# Sheet-aa.net
KiCad netlist of a schematic drawn in Altium Designer
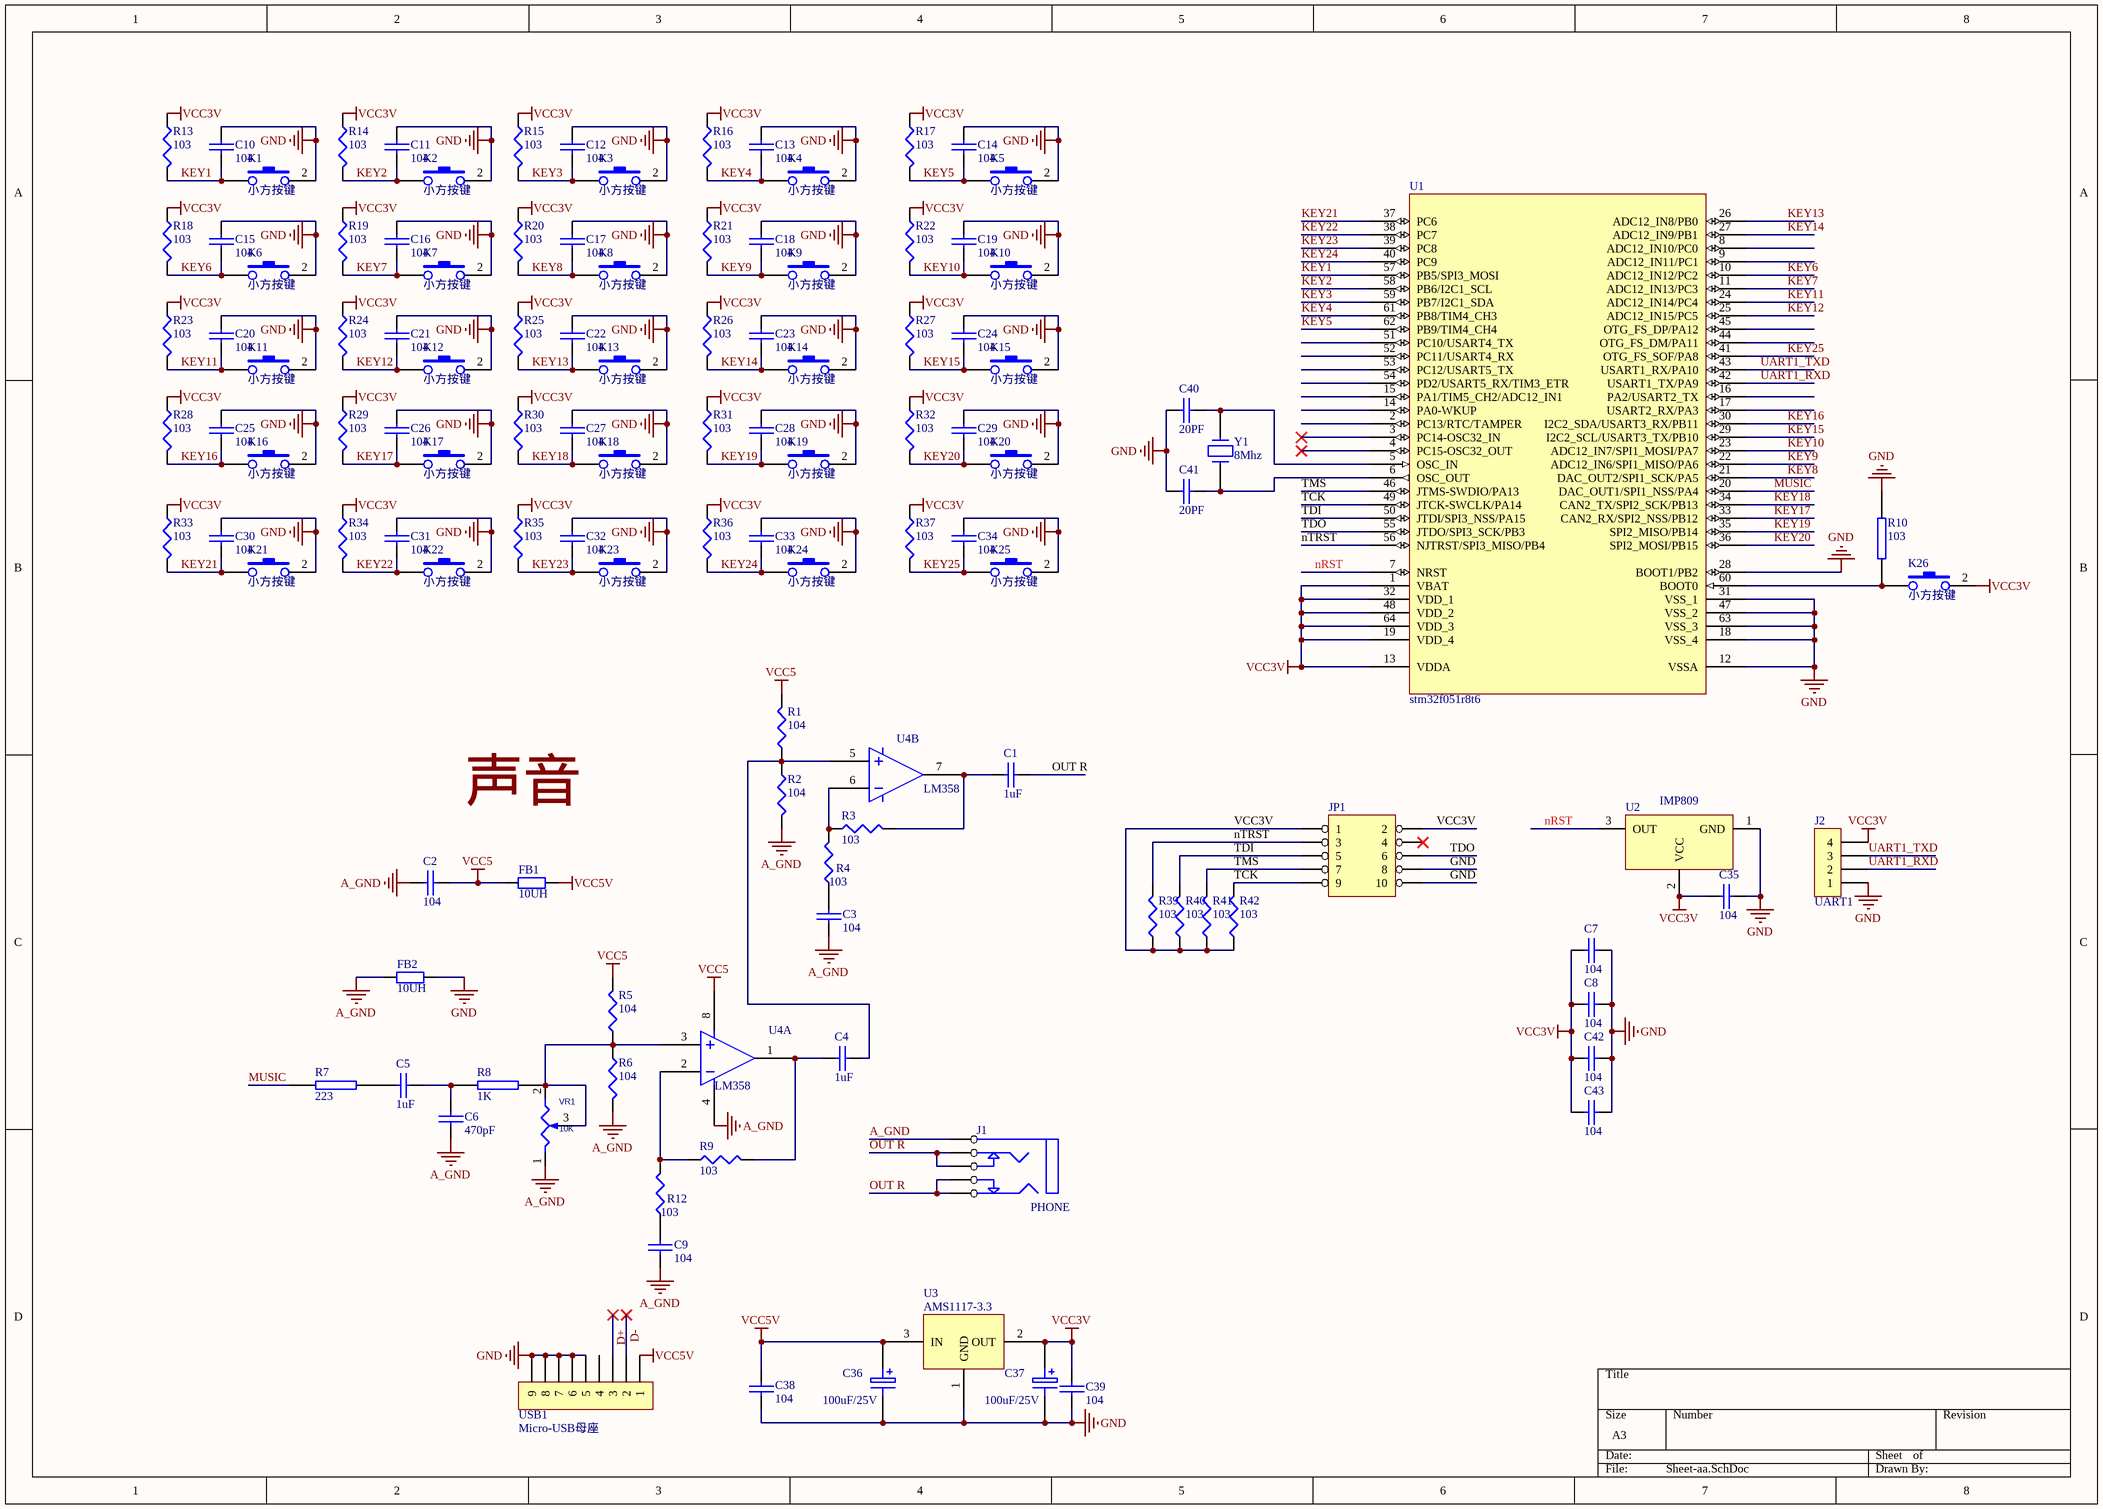
[diagram p0: Sheet-aa.SchDoc]

(export (version "E")
  (design (tool "Eeschema 10.0.6"))
  (components
    (comp (ref "C1")
      (value "1uF")
      (footprint "0805C")
      (description "Capacitor")
      (libsource (lib "*") (part "CAP"))
    )
    (comp (ref "C2")
      (value "104")
      (footprint "0805C")
      (description "Capacitor")
      (libsource (lib "") (part "CAP_1"))
    )
    (comp (ref "C3")
      (value "104")
      (footprint "0805C")
      (description "Capacitor")
      (libsource (lib "*") (part "CAP"))
    )
    (comp (ref "C4")
      (value "1uF")
      (footprint "0805C")
      (description "Capacitor")
      (libsource (lib "*") (part "CAP"))
    )
    (comp (ref "C5")
      (value "1uF")
      (footprint "0805C")
      (description "Capacitor")
      (libsource (lib "*") (part "CAP"))
    )
    (comp (ref "C6")
      (value "470pF")
      (footprint "0805C")
      (description "Capacitor")
      (libsource (lib "*") (part "CAP"))
    )
    (comp (ref "C7") (value "104") (description "Capacitor") (libsource (lib "常用分立器件") (part "CAP")))
    (comp (ref "C8") (value "104") (description "Capacitor") (libsource (lib "常用分立器件") (part "CAP")))
    (comp (ref "C9")
      (value "104")
      (footprint "0805C")
      (description "Capacitor")
      (libsource (lib "*") (part "CAP"))
    )
    (comp (ref "C10")
      (value "104")
      (footprint "0805C")
      (description "Capacitor")
      (libsource (lib "*") (part "CAP"))
    )
    (comp (ref "C11")
      (value "104")
      (footprint "0805C")
      (description "Capacitor")
      (libsource (lib "*") (part "CAP"))
    )
    (comp (ref "C12")
      (value "104")
      (footprint "0805C")
      (description "Capacitor")
      (libsource (lib "*") (part "CAP"))
    )
    (comp (ref "C13")
      (value "104")
      (footprint "0805C")
      (description "Capacitor")
      (libsource (lib "*") (part "CAP"))
    )
    (comp (ref "C14")
      (value "104")
      (footprint "0805C")
      (description "Capacitor")
      (libsource (lib "*") (part "CAP"))
    )
    (comp (ref "C15")
      (value "104")
      (footprint "0805C")
      (description "Capacitor")
      (libsource (lib "*") (part "CAP"))
    )
    (comp (ref "C16")
      (value "104")
      (footprint "0805C")
      (description "Capacitor")
      (libsource (lib "*") (part "CAP"))
    )
    (comp (ref "C17")
      (value "104")
      (footprint "0805C")
      (description "Capacitor")
      (libsource (lib "*") (part "CAP"))
    )
    (comp (ref "C18")
      (value "104")
      (footprint "0805C")
      (description "Capacitor")
      (libsource (lib "*") (part "CAP"))
    )
    (comp (ref "C19")
      (value "104")
      (footprint "0805C")
      (description "Capacitor")
      (libsource (lib "*") (part "CAP"))
    )
    (comp (ref "C20")
      (value "104")
      (footprint "0805C")
      (description "Capacitor")
      (libsource (lib "*") (part "CAP"))
    )
    (comp (ref "C21")
      (value "104")
      (footprint "0805C")
      (description "Capacitor")
      (libsource (lib "*") (part "CAP"))
    )
    (comp (ref "C22")
      (value "104")
      (footprint "0805C")
      (description "Capacitor")
      (libsource (lib "*") (part "CAP"))
    )
    (comp (ref "C23")
      (value "104")
      (footprint "0805C")
      (description "Capacitor")
      (libsource (lib "*") (part "CAP"))
    )
    (comp (ref "C24")
      (value "104")
      (footprint "0805C")
      (description "Capacitor")
      (libsource (lib "*") (part "CAP"))
    )
    (comp (ref "C25")
      (value "104")
      (footprint "0805C")
      (description "Capacitor")
      (libsource (lib "*") (part "CAP"))
    )
    (comp (ref "C26")
      (value "104")
      (footprint "0805C")
      (description "Capacitor")
      (libsource (lib "*") (part "CAP"))
    )
    (comp (ref "C27")
      (value "104")
      (footprint "0805C")
      (description "Capacitor")
      (libsource (lib "*") (part "CAP"))
    )
    (comp (ref "C28")
      (value "104")
      (footprint "0805C")
      (description "Capacitor")
      (libsource (lib "*") (part "CAP"))
    )
    (comp (ref "C29")
      (value "104")
      (footprint "0805C")
      (description "Capacitor")
      (libsource (lib "*") (part "CAP"))
    )
    (comp (ref "C30")
      (value "104")
      (footprint "0805C")
      (description "Capacitor")
      (libsource (lib "*") (part "CAP"))
    )
    (comp (ref "C31")
      (value "104")
      (footprint "0805C")
      (description "Capacitor")
      (libsource (lib "*") (part "CAP"))
    )
    (comp (ref "C32")
      (value "104")
      (footprint "0805C")
      (description "Capacitor")
      (libsource (lib "*") (part "CAP"))
    )
    (comp (ref "C33")
      (value "104")
      (footprint "0805C")
      (description "Capacitor")
      (libsource (lib "*") (part "CAP"))
    )
    (comp (ref "C34")
      (value "104")
      (footprint "0805C")
      (description "Capacitor")
      (libsource (lib "*") (part "CAP"))
    )
    (comp (ref "C35") (value "104") (description "Capacitor") (libsource (lib "常用分立器件") (part "CAP")))
    (comp (ref "C36")
      (value "100uF/25V")
      (footprint "1016V")
      (description "Electrolytic Capacitor")
      (libsource (lib "*") (part "ELECTRO1"))
    )
    (comp (ref "C37")
      (value "100uF/25V")
      (footprint "1016V")
      (description "Electrolytic Capacitor")
      (libsource (lib "*") (part "ELECTRO1"))
    )
    (comp (ref "C38")
      (value "104")
      (footprint "0805C")
      (description "Capacitor")
      (libsource (lib "") (part "CAP_1"))
    )
    (comp (ref "C39")
      (value "104")
      (footprint "0805C")
      (description "Capacitor")
      (libsource (lib "") (part "CAP_1"))
    )
    (comp (ref "C40")
      (value "20PF")
      (footprint "0805C")
      (description "Capacitor")
      (libsource (lib "常用分立器件") (part "CAP"))
    )
    (comp (ref "C41")
      (value "20PF")
      (footprint "0805C")
      (description "Capacitor")
      (libsource (lib "常用分立器件") (part "CAP"))
    )
    (comp (ref "C42") (value "104") (description "Capacitor") (libsource (lib "常用分立器件") (part "CAP")))
    (comp (ref "C43") (value "104") (description "Capacitor") (libsource (lib "常用分立器件") (part "CAP")))
    (comp (ref "FB1")
      (value "10UH")
      (footprint "0805")
      (description "Resistor")
      (fields (field (name "Comment") "Res2") (field (name "PUBLISHER") "Altium Limited"))
      (libsource (lib "Miscellaneous Devices") (part "Res2"))
    )
    (comp (ref "FB2")
      (value "10UH")
      (footprint "0805")
      (description "Resistor")
      (fields (field (name "Comment") "Res2") (field (name "PUBLISHER") "Altium Limited"))
      (libsource (lib "Miscellaneous Devices") (part "Res2"))
    )
    (comp (ref "J1") (value "PHONE") (footprint "SOUND-2") (libsource (lib "*") (part "PHONEJACK STEREO SW")))
    (comp (ref "J2")
      (value "UART1")
      (footprint "4SIP4")
      (description "Connector")
      (libsource (lib "*") (part "CON4"))
    )
    (comp (ref "JP1") (value "~") (footprint "JYNJ_10") (libsource (lib "*") (part "HEADER 5X2")))
    (comp (ref "K1")
      (value "小方按键")
      (footprint "4KEY-1")
      (description "小方按键6*6")
      (libsource (lib "常用") (part "SW-PB"))
    )
    (comp (ref "K2")
      (value "小方按键")
      (footprint "4KEY-1")
      (description "小方按键6*6")
      (libsource (lib "常用") (part "SW-PB"))
    )
    (comp (ref "K3")
      (value "小方按键")
      (footprint "4KEY-1")
      (description "小方按键6*6")
      (libsource (lib "常用") (part "SW-PB"))
    )
    (comp (ref "K4")
      (value "小方按键")
      (footprint "4KEY-1")
      (description "小方按键6*6")
      (libsource (lib "常用") (part "SW-PB"))
    )
    (comp (ref "K5")
      (value "小方按键")
      (footprint "4KEY-1")
      (description "小方按键6*6")
      (libsource (lib "常用") (part "SW-PB"))
    )
    (comp (ref "K6")
      (value "小方按键")
      (footprint "4KEY-1")
      (description "小方按键6*6")
      (libsource (lib "常用") (part "SW-PB"))
    )
    (comp (ref "K7")
      (value "小方按键")
      (footprint "4KEY-1")
      (description "小方按键6*6")
      (libsource (lib "常用") (part "SW-PB"))
    )
    (comp (ref "K8")
      (value "小方按键")
      (footprint "4KEY-1")
      (description "小方按键6*6")
      (libsource (lib "常用") (part "SW-PB"))
    )
    (comp (ref "K9")
      (value "小方按键")
      (footprint "4KEY-1")
      (description "小方按键6*6")
      (libsource (lib "常用") (part "SW-PB"))
    )
    (comp (ref "K10")
      (value "小方按键")
      (footprint "4KEY-1")
      (description "小方按键6*6")
      (libsource (lib "常用") (part "SW-PB"))
    )
    (comp (ref "K11")
      (value "小方按键")
      (footprint "4KEY-1")
      (description "小方按键6*6")
      (libsource (lib "常用") (part "SW-PB"))
    )
    (comp (ref "K12")
      (value "小方按键")
      (footprint "4KEY-1")
      (description "小方按键6*6")
      (libsource (lib "常用") (part "SW-PB"))
    )
    (comp (ref "K13")
      (value "小方按键")
      (footprint "4KEY-1")
      (description "小方按键6*6")
      (libsource (lib "常用") (part "SW-PB"))
    )
    (comp (ref "K14")
      (value "小方按键")
      (footprint "4KEY-1")
      (description "小方按键6*6")
      (libsource (lib "常用") (part "SW-PB"))
    )
    (comp (ref "K15")
      (value "小方按键")
      (footprint "4KEY-1")
      (description "小方按键6*6")
      (libsource (lib "常用") (part "SW-PB"))
    )
    (comp (ref "K16")
      (value "小方按键")
      (footprint "4KEY-1")
      (description "小方按键6*6")
      (libsource (lib "常用") (part "SW-PB"))
    )
    (comp (ref "K17")
      (value "小方按键")
      (footprint "4KEY-1")
      (description "小方按键6*6")
      (libsource (lib "常用") (part "SW-PB"))
    )
    (comp (ref "K18")
      (value "小方按键")
      (footprint "4KEY-1")
      (description "小方按键6*6")
      (libsource (lib "常用") (part "SW-PB"))
    )
    (comp (ref "K19")
      (value "小方按键")
      (footprint "4KEY-1")
      (description "小方按键6*6")
      (libsource (lib "常用") (part "SW-PB"))
    )
    (comp (ref "K20")
      (value "小方按键")
      (footprint "4KEY-1")
      (description "小方按键6*6")
      (libsource (lib "常用") (part "SW-PB"))
    )
    (comp (ref "K21")
      (value "小方按键")
      (footprint "4KEY-1")
      (description "小方按键6*6")
      (libsource (lib "常用") (part "SW-PB"))
    )
    (comp (ref "K22")
      (value "小方按键")
      (footprint "4KEY-1")
      (description "小方按键6*6")
      (libsource (lib "常用") (part "SW-PB"))
    )
    (comp (ref "K23")
      (value "小方按键")
      (footprint "4KEY-1")
      (description "小方按键6*6")
      (libsource (lib "常用") (part "SW-PB"))
    )
    (comp (ref "K24")
      (value "小方按键")
      (footprint "4KEY-1")
      (description "小方按键6*6")
      (libsource (lib "常用") (part "SW-PB"))
    )
    (comp (ref "K25")
      (value "小方按键")
      (footprint "4KEY-1")
      (description "小方按键6*6")
      (libsource (lib "常用") (part "SW-PB"))
    )
    (comp (ref "K26")
      (value "小方按键")
      (footprint "4KEY-1")
      (description "小方按键6*6")
      (libsource (lib "常用") (part "SW-PB"))
    )
    (comp (ref "R1")
      (value "104")
      (footprint "0805R")
      (description "直插电阻")
      (libsource (lib "常用") (part "RES1"))
    )
    (comp (ref "R2")
      (value "104")
      (footprint "0805R")
      (description "直插电阻")
      (libsource (lib "常用") (part "RES1"))
    )
    (comp (ref "R3")
      (value "103")
      (footprint "0805R")
      (description "直插电阻")
      (libsource (lib "常用") (part "RES1"))
    )
    (comp (ref "R4")
      (value "103")
      (footprint "0805R")
      (description "直插电阻")
      (libsource (lib "常用") (part "RES1"))
    )
    (comp (ref "R5")
      (value "104")
      (footprint "0805R")
      (description "直插电阻")
      (libsource (lib "常用") (part "RES1"))
    )
    (comp (ref "R6")
      (value "104")
      (footprint "0805R")
      (description "直插电阻")
      (libsource (lib "常用") (part "RES1"))
    )
    (comp (ref "R7") (value "223") (footprint "0805R") (libsource (lib "*") (part "RES2")))
    (comp (ref "R8") (value "1K") (footprint "0805R") (libsource (lib "*") (part "RES2")))
    (comp (ref "R9")
      (value "103")
      (footprint "0805R")
      (description "直插电阻")
      (libsource (lib "常用") (part "RES1"))
    )
    (comp (ref "R10") (value "103") (footprint "0805R") (libsource (lib "*") (part "RES2")))
    (comp (ref "R12")
      (value "103")
      (footprint "0805R")
      (description "直插电阻")
      (libsource (lib "常用") (part "RES1"))
    )
    (comp (ref "R13")
      (value "103")
      (footprint "0805R")
      (description "直插电阻")
      (libsource (lib "常用") (part "RES1"))
    )
    (comp (ref "R14")
      (value "103")
      (footprint "0805R")
      (description "直插电阻")
      (libsource (lib "常用") (part "RES1"))
    )
    (comp (ref "R15")
      (value "103")
      (footprint "0805R")
      (description "直插电阻")
      (libsource (lib "常用") (part "RES1"))
    )
    (comp (ref "R16")
      (value "103")
      (footprint "0805R")
      (description "直插电阻")
      (libsource (lib "常用") (part "RES1"))
    )
    (comp (ref "R17")
      (value "103")
      (footprint "0805R")
      (description "直插电阻")
      (libsource (lib "常用") (part "RES1"))
    )
    (comp (ref "R18")
      (value "103")
      (footprint "0805R")
      (description "直插电阻")
      (libsource (lib "常用") (part "RES1"))
    )
    (comp (ref "R19")
      (value "103")
      (footprint "0805R")
      (description "直插电阻")
      (libsource (lib "常用") (part "RES1"))
    )
    (comp (ref "R20")
      (value "103")
      (footprint "0805R")
      (description "直插电阻")
      (libsource (lib "常用") (part "RES1"))
    )
    (comp (ref "R21")
      (value "103")
      (footprint "0805R")
      (description "直插电阻")
      (libsource (lib "常用") (part "RES1"))
    )
    (comp (ref "R22")
      (value "103")
      (footprint "0805R")
      (description "直插电阻")
      (libsource (lib "常用") (part "RES1"))
    )
    (comp (ref "R23")
      (value "103")
      (footprint "0805R")
      (description "直插电阻")
      (libsource (lib "常用") (part "RES1"))
    )
    (comp (ref "R24")
      (value "103")
      (footprint "0805R")
      (description "直插电阻")
      (libsource (lib "常用") (part "RES1"))
    )
    (comp (ref "R25")
      (value "103")
      (footprint "0805R")
      (description "直插电阻")
      (libsource (lib "常用") (part "RES1"))
    )
    (comp (ref "R26")
      (value "103")
      (footprint "0805R")
      (description "直插电阻")
      (libsource (lib "常用") (part "RES1"))
    )
    (comp (ref "R27")
      (value "103")
      (footprint "0805R")
      (description "直插电阻")
      (libsource (lib "常用") (part "RES1"))
    )
    (comp (ref "R28")
      (value "103")
      (footprint "0805R")
      (description "直插电阻")
      (libsource (lib "常用") (part "RES1"))
    )
    (comp (ref "R29")
      (value "103")
      (footprint "0805R")
      (description "直插电阻")
      (libsource (lib "常用") (part "RES1"))
    )
    (comp (ref "R30")
      (value "103")
      (footprint "0805R")
      (description "直插电阻")
      (libsource (lib "常用") (part "RES1"))
    )
    (comp (ref "R31")
      (value "103")
      (footprint "0805R")
      (description "直插电阻")
      (libsource (lib "常用") (part "RES1"))
    )
    (comp (ref "R32")
      (value "103")
      (footprint "0805R")
      (description "直插电阻")
      (libsource (lib "常用") (part "RES1"))
    )
    (comp (ref "R33")
      (value "103")
      (footprint "0805R")
      (description "直插电阻")
      (libsource (lib "常用") (part "RES1"))
    )
    (comp (ref "R34")
      (value "103")
      (footprint "0805R")
      (description "直插电阻")
      (libsource (lib "常用") (part "RES1"))
    )
    (comp (ref "R35")
      (value "103")
      (footprint "0805R")
      (description "直插电阻")
      (libsource (lib "常用") (part "RES1"))
    )
    (comp (ref "R36")
      (value "103")
      (footprint "0805R")
      (description "直插电阻")
      (libsource (lib "常用") (part "RES1"))
    )
    (comp (ref "R37")
      (value "103")
      (footprint "0805R")
      (description "直插电阻")
      (libsource (lib "常用") (part "RES1"))
    )
    (comp (ref "R39")
      (value "103")
      (footprint "0805R")
      (description "直插电阻")
      (libsource (lib "常用") (part "RES1"))
    )
    (comp (ref "R40")
      (value "103")
      (footprint "0805R")
      (description "直插电阻")
      (libsource (lib "常用") (part "RES1"))
    )
    (comp (ref "R41")
      (value "103")
      (footprint "0805R")
      (description "直插电阻")
      (libsource (lib "常用") (part "RES1"))
    )
    (comp (ref "R42")
      (value "103")
      (footprint "0805R")
      (description "直插电阻")
      (libsource (lib "常用") (part "RES1"))
    )
    (comp (ref "U1")
      (value "stm32f051r8t6")
      (footprint "LC-LQFP-64_10x10x05P")
      (description "32位STM单片机")
      (fields (field (name "版权归属") "源创客"))
      (libsource (lib "2.1   - STM32系列单片机") (part "STM32F105RB_1"))
    )
    (comp (ref "U2") (value "IMP809") (footprint "SOT23") (libsource (lib "常用分立器件") (part "IMP809")))
    (comp (ref "U3") (value "AMS1117-3.3") (footprint "to-252") (libsource (lib "*") (part "LM1117")))
    (comp (ref "U4") (value "LM358") (footprint "SOP8") (libsource (lib "*") (part "LM139")))
    (comp (ref "USB1")
      (value "Micro-USB母座")
      (footprint "Micro-USB")
      (description "Connector")
      (libsource (lib "接口端子类") (part "CON9"))
    )
    (comp (ref "VR1") (value "10K") (libsource (lib "*") (part "RESISTOR VAR")))
    (comp (ref "Y1")
      (value "8Mhz")
      (footprint "2XTAL")
      (description "Crystal")
      (libsource (lib "常用分立器件") (part "CRYSTAL"))
    )
  )
  (nets
    (net (code "1") (name "/D+") (class "Default")
      (node (ref "USB1") (pin "3") (pinfunction "3_3") (pintype "passive+no_connect"))
    )
    (net (code "2") (name "/D-") (class "Default")
      (node (ref "USB1") (pin "2") (pinfunction "2_2") (pintype "passive+no_connect"))
    )
    (net (code "3") (name "/KEY1") (class "Default")
      (node (ref "C10") (pin "2") (pinfunction "2_2") (pintype "passive"))
      (node (ref "K1") (pin "1") (pinfunction "1_1") (pintype "passive"))
      (node (ref "R13") (pin "2") (pintype "passive"))
      (node (ref "U1") (pin "57") (pinfunction "PB5/SPI3_MOSI_57") (pintype "bidirectional"))
    )
    (net (code "4") (name "/KEY2") (class "Default")
      (node (ref "C11") (pin "2") (pinfunction "2_2") (pintype "passive"))
      (node (ref "K2") (pin "1") (pinfunction "1_1") (pintype "passive"))
      (node (ref "R14") (pin "2") (pintype "passive"))
      (node (ref "U1") (pin "58") (pinfunction "PB6/I2C1_SCL_58") (pintype "bidirectional"))
    )
    (net (code "5") (name "/KEY3") (class "Default")
      (node (ref "C12") (pin "2") (pinfunction "2_2") (pintype "passive"))
      (node (ref "K3") (pin "1") (pinfunction "1_1") (pintype "passive"))
      (node (ref "R15") (pin "2") (pintype "passive"))
      (node (ref "U1") (pin "59") (pinfunction "PB7/I2C1_SDA_59") (pintype "bidirectional"))
    )
    (net (code "6") (name "/KEY4") (class "Default")
      (node (ref "C13") (pin "2") (pinfunction "2_2") (pintype "passive"))
      (node (ref "K4") (pin "1") (pinfunction "1_1") (pintype "passive"))
      (node (ref "R16") (pin "2") (pintype "passive"))
      (node (ref "U1") (pin "61") (pinfunction "PB8/TIM4_CH3_61") (pintype "bidirectional"))
    )
    (net (code "7") (name "/KEY5") (class "Default")
      (node (ref "C14") (pin "2") (pinfunction "2_2") (pintype "passive"))
      (node (ref "K5") (pin "1") (pinfunction "1_1") (pintype "passive"))
      (node (ref "R17") (pin "2") (pintype "passive"))
      (node (ref "U1") (pin "62") (pinfunction "PB9/TIM4_CH4_62") (pintype "bidirectional"))
    )
    (net (code "8") (name "/KEY6") (class "Default")
      (node (ref "C15") (pin "2") (pinfunction "2_2") (pintype "passive"))
      (node (ref "K6") (pin "1") (pinfunction "1_1") (pintype "passive"))
      (node (ref "R18") (pin "2") (pintype "passive"))
      (node (ref "U1") (pin "10") (pinfunction "ADC12_IN12/PC2_10") (pintype "bidirectional"))
    )
    (net (code "9") (name "/KEY7") (class "Default")
      (node (ref "C16") (pin "2") (pinfunction "2_2") (pintype "passive"))
      (node (ref "K7") (pin "1") (pinfunction "1_1") (pintype "passive"))
      (node (ref "R19") (pin "2") (pintype "passive"))
      (node (ref "U1") (pin "11") (pinfunction "ADC12_IN13/PC3_11") (pintype "bidirectional"))
    )
    (net (code "10") (name "/KEY8") (class "Default")
      (node (ref "C17") (pin "2") (pinfunction "2_2") (pintype "passive"))
      (node (ref "K8") (pin "1") (pinfunction "1_1") (pintype "passive"))
      (node (ref "R20") (pin "2") (pintype "passive"))
      (node (ref "U1") (pin "21") (pinfunction "DAC_OUT2/SPI1_SCK/PA5_21") (pintype "bidirectional"))
    )
    (net (code "11") (name "/KEY9") (class "Default")
      (node (ref "C18") (pin "2") (pinfunction "2_2") (pintype "passive"))
      (node (ref "K9") (pin "1") (pinfunction "1_1") (pintype "passive"))
      (node (ref "R21") (pin "2") (pintype "passive"))
      (node (ref "U1") (pin "22") (pinfunction "ADC12_IN6/SPI1_MISO/PA6_22") (pintype "bidirectional"))
    )
    (net (code "12") (name "/KEY10") (class "Default")
      (node (ref "C19") (pin "2") (pinfunction "2_2") (pintype "passive"))
      (node (ref "K10") (pin "1") (pinfunction "1_1") (pintype "passive"))
      (node (ref "R22") (pin "2") (pintype "passive"))
      (node (ref "U1") (pin "23") (pinfunction "ADC12_IN7/SPI1_MOSI/PA7_23") (pintype "bidirectional"))
    )
    (net (code "13") (name "/KEY11") (class "Default")
      (node (ref "C20") (pin "2") (pinfunction "2_2") (pintype "passive"))
      (node (ref "K11") (pin "1") (pinfunction "1_1") (pintype "passive"))
      (node (ref "R23") (pin "2") (pintype "passive"))
      (node (ref "U1") (pin "24") (pinfunction "ADC12_IN14/PC4_24") (pintype "bidirectional"))
    )
    (net (code "14") (name "/KEY12") (class "Default")
      (node (ref "C21") (pin "2") (pinfunction "2_2") (pintype "passive"))
      (node (ref "K12") (pin "1") (pinfunction "1_1") (pintype "passive"))
      (node (ref "R24") (pin "2") (pintype "passive"))
      (node (ref "U1") (pin "25") (pinfunction "ADC12_IN15/PC5_25") (pintype "bidirectional"))
    )
    (net (code "15") (name "/KEY13") (class "Default")
      (node (ref "C22") (pin "2") (pinfunction "2_2") (pintype "passive"))
      (node (ref "K13") (pin "1") (pinfunction "1_1") (pintype "passive"))
      (node (ref "R25") (pin "2") (pintype "passive"))
      (node (ref "U1") (pin "26") (pinfunction "ADC12_IN8/PB0_26") (pintype "bidirectional"))
    )
    (net (code "16") (name "/KEY14") (class "Default")
      (node (ref "C23") (pin "2") (pinfunction "2_2") (pintype "passive"))
      (node (ref "K14") (pin "1") (pinfunction "1_1") (pintype "passive"))
      (node (ref "R26") (pin "2") (pintype "passive"))
      (node (ref "U1") (pin "27") (pinfunction "ADC12_IN9/PB1_27") (pintype "bidirectional"))
    )
    (net (code "17") (name "/KEY15") (class "Default")
      (node (ref "C24") (pin "2") (pinfunction "2_2") (pintype "passive"))
      (node (ref "K15") (pin "1") (pinfunction "1_1") (pintype "passive"))
      (node (ref "R27") (pin "2") (pintype "passive"))
      (node (ref "U1") (pin "29") (pinfunction "I2C2_SCL/USART3_TX/PB10_29") (pintype "bidirectional"))
    )
    (net (code "18") (name "/KEY16") (class "Default")
      (node (ref "C25") (pin "2") (pinfunction "2_2") (pintype "passive"))
      (node (ref "K16") (pin "1") (pinfunction "1_1") (pintype "passive"))
      (node (ref "R28") (pin "2") (pintype "passive"))
      (node (ref "U1") (pin "30") (pinfunction "I2C2_SDA/USART3_RX/PB11_30") (pintype "bidirectional"))
    )
    (net (code "19") (name "/KEY17") (class "Default")
      (node (ref "C26") (pin "2") (pinfunction "2_2") (pintype "passive"))
      (node (ref "K17") (pin "1") (pinfunction "1_1") (pintype "passive"))
      (node (ref "R29") (pin "2") (pintype "passive"))
      (node (ref "U1") (pin "33") (pinfunction "CAN2_RX/SPI2_NSS/PB12_33") (pintype "bidirectional"))
    )
    (net (code "20") (name "/KEY18") (class "Default")
      (node (ref "C27") (pin "2") (pinfunction "2_2") (pintype "passive"))
      (node (ref "K18") (pin "1") (pinfunction "1_1") (pintype "passive"))
      (node (ref "R30") (pin "2") (pintype "passive"))
      (node (ref "U1") (pin "34") (pinfunction "CAN2_TX/SPI2_SCK/PB13_34") (pintype "bidirectional"))
    )
    (net (code "21") (name "/KEY19") (class "Default")
      (node (ref "C28") (pin "2") (pinfunction "2_2") (pintype "passive"))
      (node (ref "K19") (pin "1") (pinfunction "1_1") (pintype "passive"))
      (node (ref "R31") (pin "2") (pintype "passive"))
      (node (ref "U1") (pin "35") (pinfunction "SPI2_MISO/PB14_35") (pintype "bidirectional"))
    )
    (net (code "22") (name "/KEY20") (class "Default")
      (node (ref "C29") (pin "2") (pinfunction "2_2") (pintype "passive"))
      (node (ref "K20") (pin "1") (pinfunction "1_1") (pintype "passive"))
      (node (ref "R32") (pin "2") (pintype "passive"))
      (node (ref "U1") (pin "36") (pinfunction "SPI2_MOSI/PB15_36") (pintype "bidirectional"))
    )
    (net (code "23") (name "/KEY21") (class "Default")
      (node (ref "C30") (pin "2") (pinfunction "2_2") (pintype "passive"))
      (node (ref "K21") (pin "1") (pinfunction "1_1") (pintype "passive"))
      (node (ref "R33") (pin "2") (pintype "passive"))
      (node (ref "U1") (pin "37") (pinfunction "PC6_37") (pintype "bidirectional"))
    )
    (net (code "24") (name "/KEY22") (class "Default")
      (node (ref "C31") (pin "2") (pinfunction "2_2") (pintype "passive"))
      (node (ref "K22") (pin "1") (pinfunction "1_1") (pintype "passive"))
      (node (ref "R34") (pin "2") (pintype "passive"))
      (node (ref "U1") (pin "38") (pinfunction "PC7_38") (pintype "bidirectional"))
    )
    (net (code "25") (name "/KEY23") (class "Default")
      (node (ref "C32") (pin "2") (pinfunction "2_2") (pintype "passive"))
      (node (ref "K23") (pin "1") (pinfunction "1_1") (pintype "passive"))
      (node (ref "R35") (pin "2") (pintype "passive"))
      (node (ref "U1") (pin "39") (pinfunction "PC8_39") (pintype "bidirectional"))
    )
    (net (code "26") (name "/KEY24") (class "Default")
      (node (ref "C33") (pin "2") (pinfunction "2_2") (pintype "passive"))
      (node (ref "K24") (pin "1") (pinfunction "1_1") (pintype "passive"))
      (node (ref "R36") (pin "2") (pintype "passive"))
      (node (ref "U1") (pin "40") (pinfunction "PC9_40") (pintype "bidirectional"))
    )
    (net (code "27") (name "/KEY25") (class "Default")
      (node (ref "C34") (pin "2") (pinfunction "2_2") (pintype "passive"))
      (node (ref "K25") (pin "1") (pinfunction "1_1") (pintype "passive"))
      (node (ref "R37") (pin "2") (pintype "passive"))
      (node (ref "U1") (pin "41") (pinfunction "OTG_FS_SOF/PA8_41") (pintype "bidirectional"))
    )
    (net (code "28") (name "/MUSIC") (class "Default")
      (node (ref "R7") (pin "1") (pinfunction "1_1") (pintype "passive"))
      (node (ref "U1") (pin "20") (pinfunction "DAC_OUT1/SPI1_NSS/PA4_20") (pintype "bidirectional"))
    )
    (net (code "29") (name "/OUT R") (class "Default")
      (node (ref "C1") (pin "1") (pinfunction "1_1") (pintype "passive"))
      (node (ref "J1") (pin "1") (pinfunction "A_1") (pintype "passive"))
      (node (ref "J1") (pin "2") (pinfunction "B_2") (pintype "passive"))
      (node (ref "J1") (pin "3") (pinfunction "C_3") (pintype "passive"))
      (node (ref "J1") (pin "4") (pinfunction "D_4") (pintype "passive"))
    )
    (net (code "30") (name "/TCK") (class "Default")
      (node (ref "JP1") (pin "9") (pinfunction "9_9") (pintype "passive"))
      (node (ref "R42") (pin "2") (pintype "passive"))
      (node (ref "U1") (pin "49") (pinfunction "JTCK-SWCLK/PA14_49") (pintype "bidirectional"))
    )
    (net (code "31") (name "/TDI") (class "Default")
      (node (ref "JP1") (pin "5") (pinfunction "5_5") (pintype "passive"))
      (node (ref "R40") (pin "2") (pintype "passive"))
      (node (ref "U1") (pin "50") (pinfunction "JTDI/SPI3_NSS/PA15_50") (pintype "bidirectional"))
    )
    (net (code "32") (name "/TDO") (class "Default")
      (node (ref "JP1") (pin "6") (pinfunction "6_6") (pintype "passive"))
      (node (ref "U1") (pin "55") (pinfunction "JTDO/SPI3_SCK/PB3_55") (pintype "bidirectional"))
    )
    (net (code "33") (name "/TMS") (class "Default")
      (node (ref "JP1") (pin "7") (pinfunction "7_7") (pintype "passive"))
      (node (ref "R41") (pin "2") (pintype "passive"))
      (node (ref "U1") (pin "46") (pinfunction "JTMS-SWDIO/PA13_46") (pintype "bidirectional"))
    )
    (net (code "34") (name "/UART1_RXD") (class "Default")
      (node (ref "J2") (pin "2") (pinfunction "2_2") (pintype "passive"))
      (node (ref "U1") (pin "42") (pinfunction "USART1_TX/PA9_42") (pintype "bidirectional"))
    )
    (net (code "35") (name "/UART1_TXD") (class "Default")
      (node (ref "J2") (pin "3") (pinfunction "3_3") (pintype "passive"))
      (node (ref "U1") (pin "43") (pinfunction "USART1_RX/PA10_43") (pintype "bidirectional"))
    )
    (net (code "36") (name "/nRST") (class "Default")
      (node (ref "U1") (pin "7") (pinfunction "NRST_7") (pintype "bidirectional"))
      (node (ref "U2") (pin "3") (pinfunction "OUT_3") (pintype "passive"))
    )
    (net (code "37") (name "/nTRST") (class "Default")
      (node (ref "JP1") (pin "3") (pinfunction "3_3") (pintype "passive"))
      (node (ref "R39") (pin "2") (pintype "passive"))
      (node (ref "U1") (pin "56") (pinfunction "NJTRST/SPI3_MISO/PB4_56") (pintype "bidirectional"))
    )
    (net (code "38") (name "A_GND") (class "Default")
      (node (ref "C2") (pin "1") (pinfunction "1_1") (pintype "passive"))
      (node (ref "C3") (pin "1") (pinfunction "1_1") (pintype "passive"))
      (node (ref "C6") (pin "1") (pinfunction "1_1") (pintype "passive"))
      (node (ref "C9") (pin "1") (pinfunction "1_1") (pintype "passive"))
      (node (ref "FB2") (pin "1") (pinfunction "1_1") (pintype "passive"))
      (node (ref "J1") (pin "5") (pinfunction "E_5") (pintype "passive"))
      (node (ref "R2") (pin "2") (pintype "passive"))
      (node (ref "R6") (pin "2") (pintype "passive"))
      (node (ref "U4") (pin "4") (pintype "passive"))
      (node (ref "VR1") (pin "1") (pinfunction "A_1") (pintype "passive"))
    )
    (net (code "39") (name "GND") (class "Default")
      (node (ref "C10") (pin "1") (pinfunction "1_1") (pintype "passive"))
      (node (ref "C11") (pin "1") (pinfunction "1_1") (pintype "passive"))
      (node (ref "C12") (pin "1") (pinfunction "1_1") (pintype "passive"))
      (node (ref "C13") (pin "1") (pinfunction "1_1") (pintype "passive"))
      (node (ref "C14") (pin "1") (pinfunction "1_1") (pintype "passive"))
      (node (ref "C15") (pin "1") (pinfunction "1_1") (pintype "passive"))
      (node (ref "C16") (pin "1") (pinfunction "1_1") (pintype "passive"))
      (node (ref "C17") (pin "1") (pinfunction "1_1") (pintype "passive"))
      (node (ref "C18") (pin "1") (pinfunction "1_1") (pintype "passive"))
      (node (ref "C19") (pin "1") (pinfunction "1_1") (pintype "passive"))
      (node (ref "C20") (pin "1") (pinfunction "1_1") (pintype "passive"))
      (node (ref "C21") (pin "1") (pinfunction "1_1") (pintype "passive"))
      (node (ref "C22") (pin "1") (pinfunction "1_1") (pintype "passive"))
      (node (ref "C23") (pin "1") (pinfunction "1_1") (pintype "passive"))
      (node (ref "C24") (pin "1") (pinfunction "1_1") (pintype "passive"))
      (node (ref "C25") (pin "1") (pinfunction "1_1") (pintype "passive"))
      (node (ref "C26") (pin "1") (pinfunction "1_1") (pintype "passive"))
      (node (ref "C27") (pin "1") (pinfunction "1_1") (pintype "passive"))
      (node (ref "C28") (pin "1") (pinfunction "1_1") (pintype "passive"))
      (node (ref "C29") (pin "1") (pinfunction "1_1") (pintype "passive"))
      (node (ref "C30") (pin "1") (pinfunction "1_1") (pintype "passive"))
      (node (ref "C31") (pin "1") (pinfunction "1_1") (pintype "passive"))
      (node (ref "C32") (pin "1") (pinfunction "1_1") (pintype "passive"))
      (node (ref "C33") (pin "1") (pinfunction "1_1") (pintype "passive"))
      (node (ref "C34") (pin "1") (pinfunction "1_1") (pintype "passive"))
      (node (ref "C35") (pin "2") (pinfunction "2_2") (pintype "passive"))
      (node (ref "C36") (pin "2") (pinfunction "2_2") (pintype "passive"))
      (node (ref "C37") (pin "2") (pinfunction "2_2") (pintype "passive"))
      (node (ref "C38") (pin "2") (pinfunction "2_2") (pintype "passive"))
      (node (ref "C39") (pin "2") (pinfunction "2_2") (pintype "passive"))
      (node (ref "C40") (pin "2") (pinfunction "2_2") (pintype "passive"))
      (node (ref "C41") (pin "1") (pinfunction "1_1") (pintype "passive"))
      (node (ref "C42") (pin "2") (pinfunction "2_2") (pintype "passive"))
      (node (ref "C43") (pin "2") (pinfunction "2_2") (pintype "passive"))
      (node (ref "C7") (pin "2") (pinfunction "2_2") (pintype "passive"))
      (node (ref "C8") (pin "2") (pinfunction "2_2") (pintype "passive"))
      (node (ref "FB2") (pin "2") (pinfunction "2_2") (pintype "passive"))
      (node (ref "J2") (pin "1") (pinfunction "1_1") (pintype "passive"))
      (node (ref "JP1") (pin "10") (pinfunction "10_10") (pintype "passive"))
      (node (ref "JP1") (pin "8") (pinfunction "8_8") (pintype "passive"))
      (node (ref "K1") (pin "2") (pinfunction "2_2") (pintype "passive"))
      (node (ref "K10") (pin "2") (pinfunction "2_2") (pintype "passive"))
      (node (ref "K11") (pin "2") (pinfunction "2_2") (pintype "passive"))
      (node (ref "K12") (pin "2") (pinfunction "2_2") (pintype "passive"))
      (node (ref "K13") (pin "2") (pinfunction "2_2") (pintype "passive"))
      (node (ref "K14") (pin "2") (pinfunction "2_2") (pintype "passive"))
      (node (ref "K15") (pin "2") (pinfunction "2_2") (pintype "passive"))
      (node (ref "K16") (pin "2") (pinfunction "2_2") (pintype "passive"))
      (node (ref "K17") (pin "2") (pinfunction "2_2") (pintype "passive"))
      (node (ref "K18") (pin "2") (pinfunction "2_2") (pintype "passive"))
      (node (ref "K19") (pin "2") (pinfunction "2_2") (pintype "passive"))
      (node (ref "K2") (pin "2") (pinfunction "2_2") (pintype "passive"))
      (node (ref "K20") (pin "2") (pinfunction "2_2") (pintype "passive"))
      (node (ref "K21") (pin "2") (pinfunction "2_2") (pintype "passive"))
      (node (ref "K22") (pin "2") (pinfunction "2_2") (pintype "passive"))
      (node (ref "K23") (pin "2") (pinfunction "2_2") (pintype "passive"))
      (node (ref "K24") (pin "2") (pinfunction "2_2") (pintype "passive"))
      (node (ref "K25") (pin "2") (pinfunction "2_2") (pintype "passive"))
      (node (ref "K3") (pin "2") (pinfunction "2_2") (pintype "passive"))
      (node (ref "K4") (pin "2") (pinfunction "2_2") (pintype "passive"))
      (node (ref "K5") (pin "2") (pinfunction "2_2") (pintype "passive"))
      (node (ref "K6") (pin "2") (pinfunction "2_2") (pintype "passive"))
      (node (ref "K7") (pin "2") (pinfunction "2_2") (pintype "passive"))
      (node (ref "K8") (pin "2") (pinfunction "2_2") (pintype "passive"))
      (node (ref "K9") (pin "2") (pinfunction "2_2") (pintype "passive"))
      (node (ref "R10") (pin "2") (pinfunction "2_2") (pintype "passive"))
      (node (ref "U1") (pin "12") (pinfunction "VSSA_12") (pintype "power_in"))
      (node (ref "U1") (pin "18") (pinfunction "VSS_4_18") (pintype "power_in"))
      (node (ref "U1") (pin "28") (pinfunction "BOOT1/PB2_28") (pintype "bidirectional"))
      (node (ref "U1") (pin "31") (pinfunction "VSS_1_31") (pintype "passive"))
      (node (ref "U1") (pin "47") (pinfunction "VSS_2_47") (pintype "passive"))
      (node (ref "U1") (pin "63") (pinfunction "VSS_3_63") (pintype "power_in"))
      (node (ref "U2") (pin "1") (pinfunction "GND_1") (pintype "passive"))
      (node (ref "U3") (pin "1") (pinfunction "GND_1") (pintype "power_in"))
      (node (ref "USB1") (pin "5") (pinfunction "5_5") (pintype "passive"))
      (node (ref "USB1") (pin "6") (pinfunction "6_6") (pintype "passive"))
      (node (ref "USB1") (pin "7") (pinfunction "7_7") (pintype "passive"))
      (node (ref "USB1") (pin "8") (pinfunction "8_8") (pintype "passive"))
      (node (ref "USB1") (pin "9") (pinfunction "9_9") (pintype "passive"))
    )
    (net (code "40") (name "Net-(C1-Pad2)") (class "Default")
      (node (ref "C1") (pin "2") (pinfunction "2_2") (pintype "passive"))
      (node (ref "R3") (pin "2") (pintype "passive"))
      (node (ref "U4") (pin "7") (pintype "passive"))
    )
    (net (code "41") (name "Net-(C3-Pad2)") (class "Default")
      (node (ref "C3") (pin "2") (pinfunction "2_2") (pintype "passive"))
      (node (ref "R4") (pin "1") (pintype "passive"))
    )
    (net (code "42") (name "Net-(C4-Pad1)") (class "Default")
      (node (ref "C4") (pin "1") (pinfunction "1_1") (pintype "passive"))
      (node (ref "R1") (pin "1") (pintype "passive"))
      (node (ref "R2") (pin "1") (pintype "passive"))
      (node (ref "U4") (pin "5") (pintype "passive"))
    )
    (net (code "43") (name "Net-(C4-Pad2)") (class "Default")
      (node (ref "C4") (pin "2") (pinfunction "2_2") (pintype "passive"))
      (node (ref "R9") (pin "2") (pintype "passive"))
      (node (ref "U4") (pin "1") (pintype "passive"))
    )
    (net (code "44") (name "Net-(C5-Pad1)") (class "Default")
      (node (ref "C5") (pin "1") (pinfunction "1_1") (pintype "passive"))
      (node (ref "C6") (pin "2") (pinfunction "2_2") (pintype "passive"))
      (node (ref "R8") (pin "1") (pinfunction "1_1") (pintype "passive"))
    )
    (net (code "45") (name "Net-(C5-Pad2)") (class "Default")
      (node (ref "C5") (pin "2") (pinfunction "2_2") (pintype "passive"))
      (node (ref "R7") (pin "2") (pinfunction "2_2") (pintype "passive"))
    )
    (net (code "46") (name "Net-(C9-Pad2)") (class "Default")
      (node (ref "C9") (pin "2") (pinfunction "2_2") (pintype "passive"))
      (node (ref "R12") (pin "1") (pintype "passive"))
    )
    (net (code "47") (name "Net-(R3-Pad1)") (class "Default")
      (node (ref "R3") (pin "1") (pintype "passive"))
      (node (ref "R4") (pin "2") (pintype "passive"))
      (node (ref "U4") (pin "6") (pintype "passive"))
    )
    (net (code "48") (name "Net-(R12-Pad2)") (class "Default")
      (node (ref "R12") (pin "2") (pintype "passive"))
      (node (ref "R9") (pin "1") (pintype "passive"))
      (node (ref "U4") (pin "2") (pintype "passive"))
    )
    (net (code "49") (name "Net-(U1-BOOT0)") (class "Default")
      (node (ref "K26") (pin "1") (pinfunction "1_1") (pintype "passive"))
      (node (ref "R10") (pin "1") (pinfunction "1_1") (pintype "passive"))
      (node (ref "U1") (pin "60") (pinfunction "BOOT0_60") (pintype "input"))
    )
    (net (code "50") (name "Net-(U1-OSC_IN)") (class "Default")
      (node (ref "C40") (pin "1") (pinfunction "1_1") (pintype "passive"))
      (node (ref "U1") (pin "5") (pinfunction "OSC_IN_5") (pintype "input"))
      (node (ref "Y1") (pin "2") (pinfunction "2_2") (pintype "passive"))
    )
    (net (code "51") (name "Net-(U1-OSC_OUT)") (class "Default")
      (node (ref "C41") (pin "2") (pinfunction "2_2") (pintype "passive"))
      (node (ref "U1") (pin "6") (pinfunction "OSC_OUT_6") (pintype "output"))
      (node (ref "Y1") (pin "1") (pinfunction "1_1") (pintype "passive"))
    )
    (net (code "52") (name "Net-(VR1-B)") (class "Default")
      (node (ref "R5") (pin "1") (pintype "passive"))
      (node (ref "R6") (pin "1") (pintype "passive"))
      (node (ref "R8") (pin "2") (pinfunction "2_2") (pintype "passive"))
      (node (ref "U4") (pin "3") (pintype "passive"))
      (node (ref "VR1") (pin "2") (pinfunction "WIPER_2") (pintype "passive"))
      (node (ref "VR1") (pin "3") (pinfunction "B_3") (pintype "passive"))
    )
    (net (code "53") (name "VCC3V") (class "Default")
      (node (ref "C35") (pin "1") (pinfunction "1_1") (pintype "passive"))
      (node (ref "C37") (pin "1") (pinfunction "1_1") (pintype "passive"))
      (node (ref "C39") (pin "1") (pinfunction "1_1") (pintype "passive"))
      (node (ref "C42") (pin "1") (pinfunction "1_1") (pintype "passive"))
      (node (ref "C43") (pin "1") (pinfunction "1_1") (pintype "passive"))
      (node (ref "C7") (pin "1") (pinfunction "1_1") (pintype "passive"))
      (node (ref "C8") (pin "1") (pinfunction "1_1") (pintype "passive"))
      (node (ref "J2") (pin "4") (pinfunction "4_4") (pintype "passive"))
      (node (ref "JP1") (pin "1") (pinfunction "1_1") (pintype "passive"))
      (node (ref "JP1") (pin "2") (pinfunction "2_2") (pintype "passive"))
      (node (ref "K26") (pin "2") (pinfunction "2_2") (pintype "passive"))
      (node (ref "R13") (pin "1") (pintype "passive"))
      (node (ref "R14") (pin "1") (pintype "passive"))
      (node (ref "R15") (pin "1") (pintype "passive"))
      (node (ref "R16") (pin "1") (pintype "passive"))
      (node (ref "R17") (pin "1") (pintype "passive"))
      (node (ref "R18") (pin "1") (pintype "passive"))
      (node (ref "R19") (pin "1") (pintype "passive"))
      (node (ref "R20") (pin "1") (pintype "passive"))
      (node (ref "R21") (pin "1") (pintype "passive"))
      (node (ref "R22") (pin "1") (pintype "passive"))
      (node (ref "R23") (pin "1") (pintype "passive"))
      (node (ref "R24") (pin "1") (pintype "passive"))
      (node (ref "R25") (pin "1") (pintype "passive"))
      (node (ref "R26") (pin "1") (pintype "passive"))
      (node (ref "R27") (pin "1") (pintype "passive"))
      (node (ref "R28") (pin "1") (pintype "passive"))
      (node (ref "R29") (pin "1") (pintype "passive"))
      (node (ref "R30") (pin "1") (pintype "passive"))
      (node (ref "R31") (pin "1") (pintype "passive"))
      (node (ref "R32") (pin "1") (pintype "passive"))
      (node (ref "R33") (pin "1") (pintype "passive"))
      (node (ref "R34") (pin "1") (pintype "passive"))
      (node (ref "R35") (pin "1") (pintype "passive"))
      (node (ref "R36") (pin "1") (pintype "passive"))
      (node (ref "R37") (pin "1") (pintype "passive"))
      (node (ref "R39") (pin "1") (pintype "passive"))
      (node (ref "R40") (pin "1") (pintype "passive"))
      (node (ref "R41") (pin "1") (pintype "passive"))
      (node (ref "R42") (pin "1") (pintype "passive"))
      (node (ref "U1") (pin "1") (pinfunction "VBAT_1") (pintype "power_in"))
      (node (ref "U1") (pin "13") (pinfunction "VDDA_13") (pintype "power_in"))
      (node (ref "U1") (pin "19") (pinfunction "VDD_4_19") (pintype "power_in"))
      (node (ref "U1") (pin "32") (pinfunction "VDD_1_32") (pintype "power_in"))
      (node (ref "U1") (pin "48") (pinfunction "VDD_2_48") (pintype "power_in"))
      (node (ref "U1") (pin "64") (pinfunction "VDD_3_64") (pintype "power_in"))
      (node (ref "U2") (pin "2") (pinfunction "VCC_2") (pintype "passive"))
      (node (ref "U3") (pin "2") (pinfunction "OUT_2") (pintype "power_in"))
    )
    (net (code "54") (name "VCC5") (class "Default")
      (node (ref "C2") (pin "2") (pinfunction "2_2") (pintype "passive"))
      (node (ref "FB1") (pin "1") (pinfunction "1_1") (pintype "passive"))
      (node (ref "R1") (pin "2") (pintype "passive"))
      (node (ref "R5") (pin "2") (pintype "passive"))
      (node (ref "U4") (pin "8") (pinfunction "VCC_8") (pintype "passive"))
    )
    (net (code "55") (name "VCC5V") (class "Default")
      (node (ref "C36") (pin "1") (pinfunction "1_1") (pintype "passive"))
      (node (ref "C38") (pin "1") (pinfunction "1_1") (pintype "passive"))
      (node (ref "FB1") (pin "2") (pinfunction "2_2") (pintype "passive"))
      (node (ref "U3") (pin "3") (pinfunction "IN_3") (pintype "power_in"))
      (node (ref "USB1") (pin "1") (pinfunction "1_1") (pintype "passive"))
    )
    (net (code "56") (name "unconnected-(JP1-Pad4)") (class "Default")
      (node (ref "JP1") (pin "4") (pinfunction "4_4") (pintype "passive+no_connect"))
    )
    (net (code "57") (name "unconnected-(U1-ADC12_IN10{slash}PC0-Pad8)") (class "Default")
      (node (ref "U1") (pin "8") (pinfunction "ADC12_IN10/PC0_8") (pintype "bidirectional"))
    )
    (net (code "58") (name "unconnected-(U1-ADC12_IN11{slash}PC1-Pad9)") (class "Default")
      (node (ref "U1") (pin "9") (pinfunction "ADC12_IN11/PC1_9") (pintype "bidirectional"))
    )
    (net (code "59") (name "unconnected-(U1-OTG_FS_DM{slash}PA11-Pad44)") (class "Default")
      (node (ref "U1") (pin "44") (pinfunction "OTG_FS_DM/PA11_44") (pintype "bidirectional"))
    )
    (net (code "60") (name "unconnected-(U1-OTG_FS_DP{slash}PA12-Pad45)") (class "Default")
      (node (ref "U1") (pin "45") (pinfunction "OTG_FS_DP/PA12_45") (pintype "bidirectional"))
    )
    (net (code "61") (name "unconnected-(U1-PA0-WKUP-Pad14)") (class "Default")
      (node (ref "U1") (pin "14") (pinfunction "PA0-WKUP_14") (pintype "bidirectional"))
    )
    (net (code "62") (name "unconnected-(U1-PA1{slash}TIM5_CH2{slash}ADC12_IN1-Pad15)") (class "Default")
      (node (ref "U1") (pin "15") (pinfunction "PA1/TIM5_CH2/ADC12_IN1_15") (pintype "bidirectional"))
    )
    (net (code "63") (name "unconnected-(U1-PA2{slash}USART2_TX-Pad16)") (class "Default")
      (node (ref "U1") (pin "16") (pinfunction "PA2/USART2_TX_16") (pintype "bidirectional"))
    )
    (net (code "64") (name "unconnected-(U1-PC10{slash}USART4_TX-Pad51)") (class "Default")
      (node (ref "U1") (pin "51") (pinfunction "PC10/USART4_TX_51") (pintype "bidirectional"))
    )
    (net (code "65") (name "unconnected-(U1-PC11{slash}USART4_RX-Pad52)") (class "Default")
      (node (ref "U1") (pin "52") (pinfunction "PC11/USART4_RX_52") (pintype "bidirectional"))
    )
    (net (code "66") (name "unconnected-(U1-PC12{slash}USART5_TX-Pad53)") (class "Default")
      (node (ref "U1") (pin "53") (pinfunction "PC12/USART5_TX_53") (pintype "bidirectional"))
    )
    (net (code "67") (name "unconnected-(U1-PC13{slash}RTC{slash}TAMPER-Pad2)") (class "Default")
      (node (ref "U1") (pin "2") (pinfunction "PC13/RTC/TAMPER_2") (pintype "bidirectional"))
    )
    (net (code "68") (name "unconnected-(U1-PC14-OSC32_IN-Pad3)") (class "Default")
      (node (ref "U1") (pin "3") (pinfunction "PC14-OSC32_IN_3") (pintype "bidirectional+no_connect"))
    )
    (net (code "69") (name "unconnected-(U1-PC15-OSC32_OUT-Pad4)") (class "Default")
      (node (ref "U1") (pin "4") (pinfunction "PC15-OSC32_OUT_4") (pintype "bidirectional+no_connect"))
    )
    (net (code "70") (name "unconnected-(U1-PD2{slash}USART5_RX{slash}TIM3_ETR-Pad54)") (class "Default")
      (node (ref "U1") (pin "54") (pinfunction "PD2/USART5_RX/TIM3_ETR_54") (pintype "bidirectional"))
    )
    (net (code "71") (name "unconnected-(U1-USART2_RX{slash}PA3-Pad17)") (class "Default")
      (node (ref "U1") (pin "17") (pinfunction "USART2_RX/PA3_17") (pintype "bidirectional"))
    )
    (net (code "72") (name "unconnected-(USB1-Pad4)") (class "Default")
      (node (ref "USB1") (pin "4") (pinfunction "4_4") (pintype "passive"))
    )
  )
)
